# Painel_V1_0_4.net
KiCad netlist of a schematic drawn in EAGLE
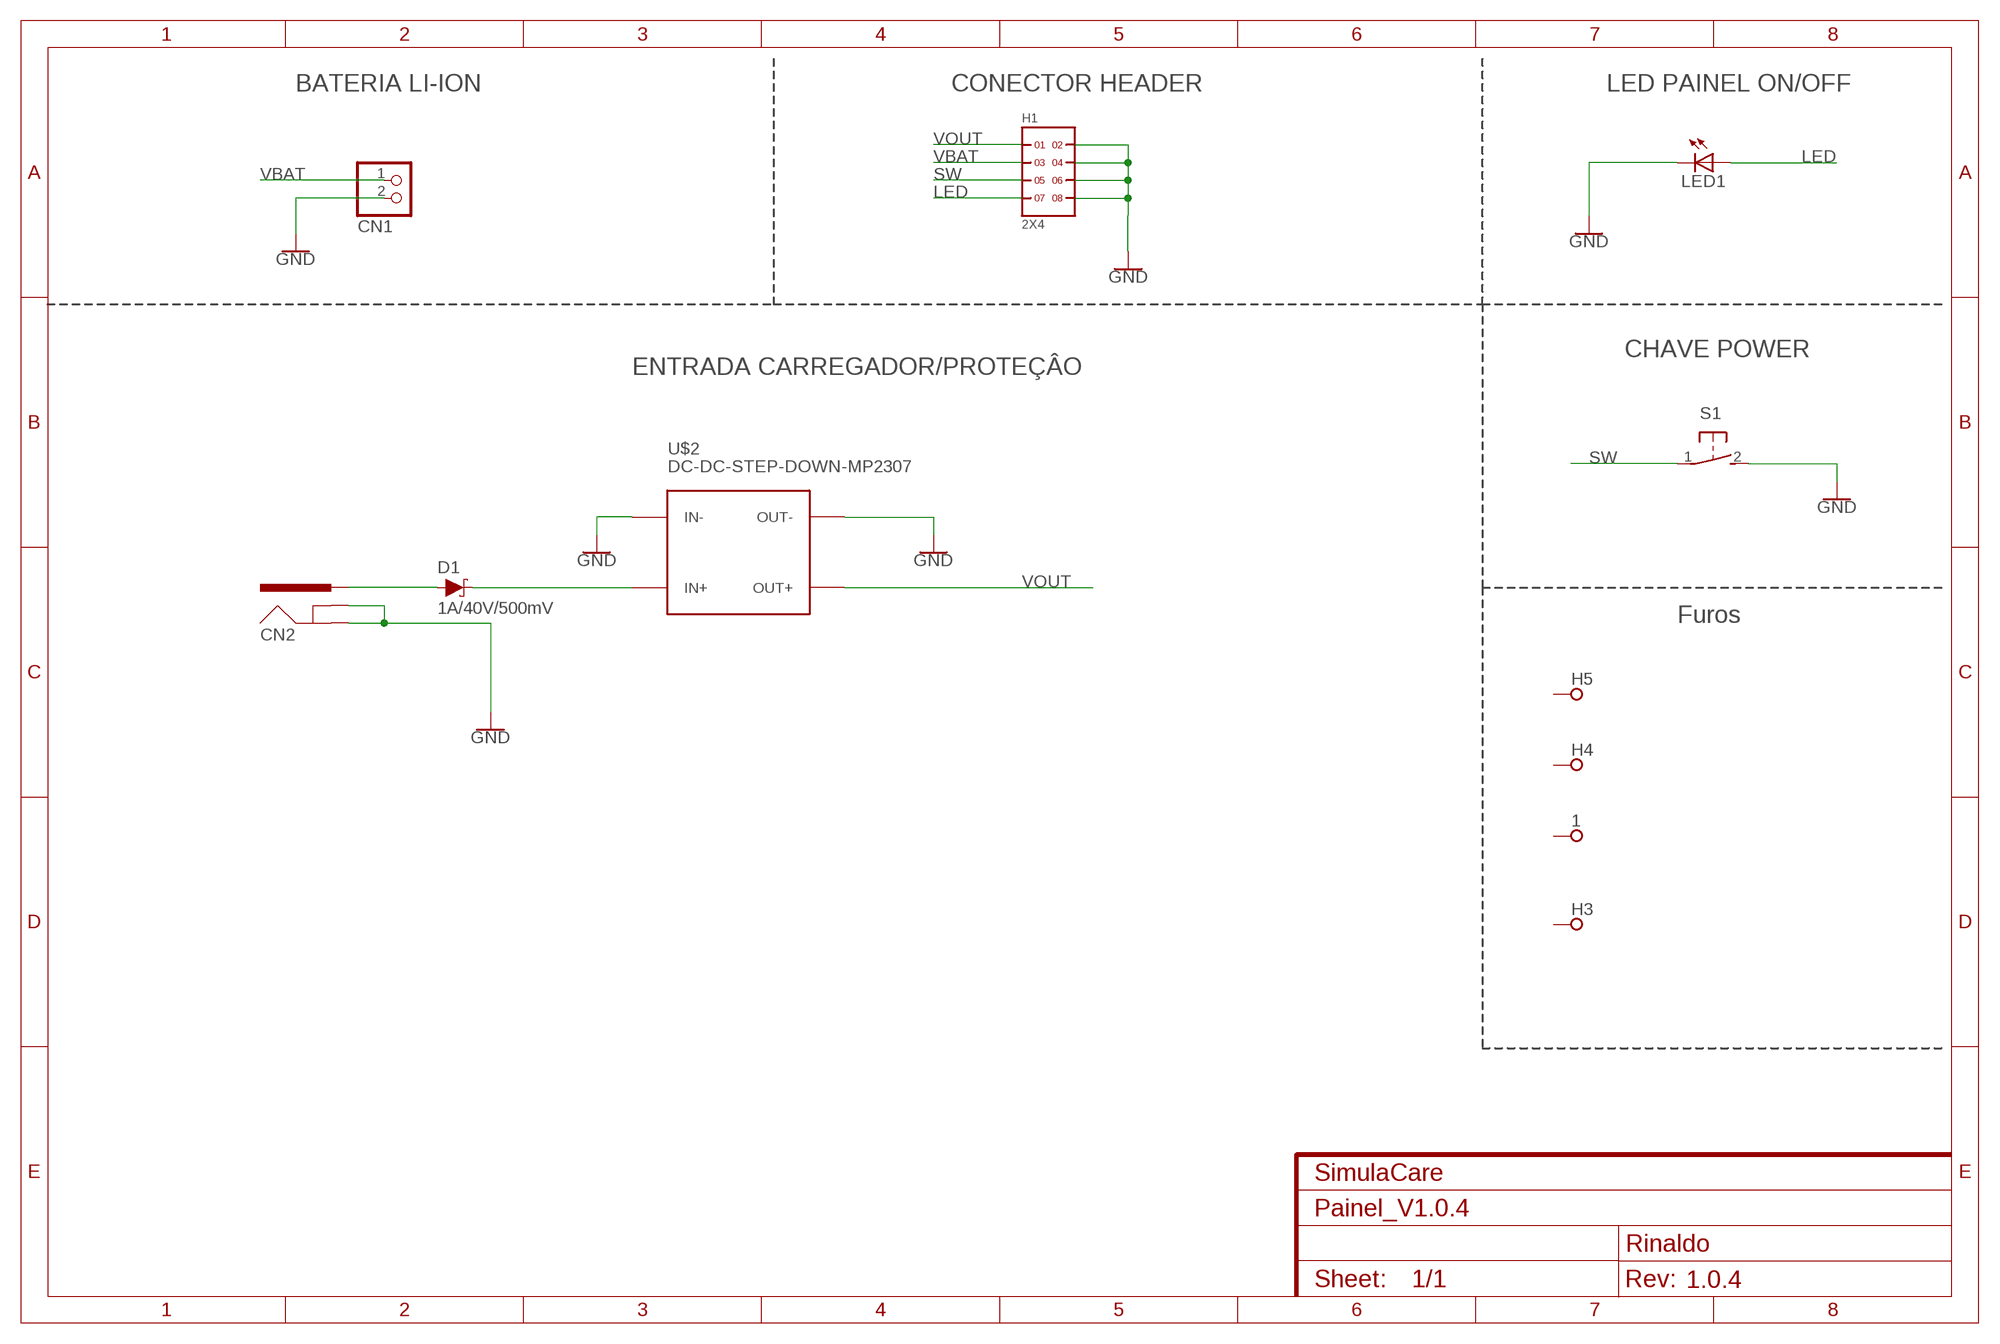
[diagram p0: schematic, sheet 1]

(export (version "E")
  (design (tool "Eeschema 10.0.6"))
  (components
    (comp (ref "1")
      (value "SPECIAL_DRILL_0.1250")
      (footprint "eagle-import:PAD_0.1250")
      (libsource (lib "eagle-import") (part "SPECIAL_DRILL_0.1250"))
    )
    (comp (ref "CN1")
      (value "JST_2PIN-THM")
      (footprint "eagle-import:JST-PH-2-THM")
      (libsource (lib "eagle-import") (part "JST_2PIN-THM"))
    )
    (comp (ref "CN2")
      (value "POWERJACK")
      (footprint "eagle-import:POWERJACK")
      (libsource (lib "eagle-import") (part "POWERJACK"))
    )
    (comp (ref "D1")
      (value "1A/40V/500mV")
      (footprint "eagle-import:SMA-DIODE")
      (libsource (lib "eagle-import") (part "DIODE-SCHOTTKY-SS14"))
    )
    (comp (ref "H1")
      (value "2X4")
      (footprint "eagle-import:2X4")
      (libsource (lib "eagle-import") (part "2X4"))
    )
    (comp (ref "H3")
      (value "SPECIAL_DRILL_0.1250")
      (footprint "eagle-import:PAD_0.1250")
      (libsource (lib "eagle-import") (part "SPECIAL_DRILL_0.1250"))
    )
    (comp (ref "H4")
      (value "SPECIAL_DRILL_0.1250")
      (footprint "eagle-import:PAD_0.1250")
      (libsource (lib "eagle-import") (part "SPECIAL_DRILL_0.1250"))
    )
    (comp (ref "H5")
      (value "SPECIAL_DRILL_0.1250")
      (footprint "eagle-import:PAD_0.1250")
      (libsource (lib "eagle-import") (part "SPECIAL_DRILL_0.1250"))
    )
    (comp (ref "LED1")
      (value "LED3MM")
      (footprint "eagle-import:LED3MM")
      (libsource (lib "eagle-import") (part "LED3MM"))
    )
    (comp (ref "S1")
      (value "31-XX")
      (footprint "eagle-import:B3F-31XX")
      (libsource (lib "eagle-import") (part "31-XX"))
    )
    (comp (ref "U$2")
      (value "DC-DC-STEP-DOWN-MP2307")
      (footprint "eagle-import:DC-DC-STEP-DOWN-MP2307")
      (libsource (lib "eagle-import") (part "DC-DC-STEP-DOWN-MP2307"))
    )
  )
  (nets
    (net (code "1") (name "/LED") (class "Default")
      (node (ref "H1") (pin "7") (pinfunction "7_7") (pintype "bidirectional"))
      (node (ref "LED1") (pin "A") (pinfunction "A_A") (pintype "passive"))
    )
    (net (code "2") (name "/SW") (class "Default")
      (node (ref "H1") (pin "5") (pinfunction "5_5") (pintype "bidirectional"))
      (node (ref "S1") (pin "1") (pinfunction "P_1") (pintype "passive"))
    )
    (net (code "3") (name "/VBAT") (class "Default")
      (node (ref "CN1") (pin "1") (pinfunction "2_1") (pintype "passive"))
      (node (ref "H1") (pin "3") (pinfunction "3_3") (pintype "bidirectional"))
    )
    (net (code "4") (name "/VOUT") (class "Default")
      (node (ref "H1") (pin "1") (pinfunction "1_1") (pintype "bidirectional"))
      (node (ref "U$2") (pin "OUT+") (pinfunction "OUT+_OUT+") (pintype "bidirectional"))
    )
    (net (code "5") (name "GND") (class "Default")
      (node (ref "CN1") (pin "2") (pinfunction "1_2") (pintype "passive"))
      (node (ref "CN2") (pin "GND") (pinfunction "GND_GND") (pintype "bidirectional"))
      (node (ref "CN2") (pin "GNDBREAK") (pinfunction "GNDBREAK_GNDBREAK") (pintype "bidirectional"))
      (node (ref "H1") (pin "2") (pinfunction "2_2") (pintype "bidirectional"))
      (node (ref "H1") (pin "4") (pinfunction "4_4") (pintype "bidirectional"))
      (node (ref "H1") (pin "6") (pinfunction "6_6") (pintype "bidirectional"))
      (node (ref "H1") (pin "8") (pinfunction "8_8") (pintype "bidirectional"))
      (node (ref "LED1") (pin "K") (pinfunction "C_K") (pintype "passive"))
      (node (ref "S1") (pin "2") (pinfunction "S_2") (pintype "passive"))
      (node (ref "U$2") (pin "IN-") (pinfunction "IN-_IN-") (pintype "bidirectional"))
      (node (ref "U$2") (pin "OUT-") (pinfunction "OUT-_OUT-") (pintype "bidirectional"))
    )
    (net (code "6") (name "Net-(CN2-PadPWR)") (class "Default")
      (node (ref "CN2") (pin "PWR") (pinfunction "PWR_PWR") (pintype "bidirectional"))
      (node (ref "D1") (pin "A") (pinfunction "A_A") (pintype "passive"))
    )
    (net (code "7") (name "Net-(D1-PadC)") (class "Default")
      (node (ref "D1") (pin "C") (pinfunction "C_C") (pintype "passive"))
      (node (ref "U$2") (pin "IN+") (pinfunction "IN+_IN+") (pintype "bidirectional"))
    )
    (net (code "8") (name "unconnected-(1-Pad1)") (class "Default")
      (node (ref "1") (pin "1") (pinfunction "1_1") (pintype "passive"))
    )
    (net (code "9") (name "unconnected-(H3-Pad1)") (class "Default")
      (node (ref "H3") (pin "1") (pinfunction "1_1") (pintype "passive"))
    )
    (net (code "10") (name "unconnected-(H4-Pad1)") (class "Default")
      (node (ref "H4") (pin "1") (pinfunction "1_1") (pintype "passive"))
    )
    (net (code "11") (name "unconnected-(H5-Pad1)") (class "Default")
      (node (ref "H5") (pin "1") (pinfunction "1_1") (pintype "passive"))
    )
  )
)
